# POWER_PCie.net
KiCad netlist of a schematic drawn in Altium Designer
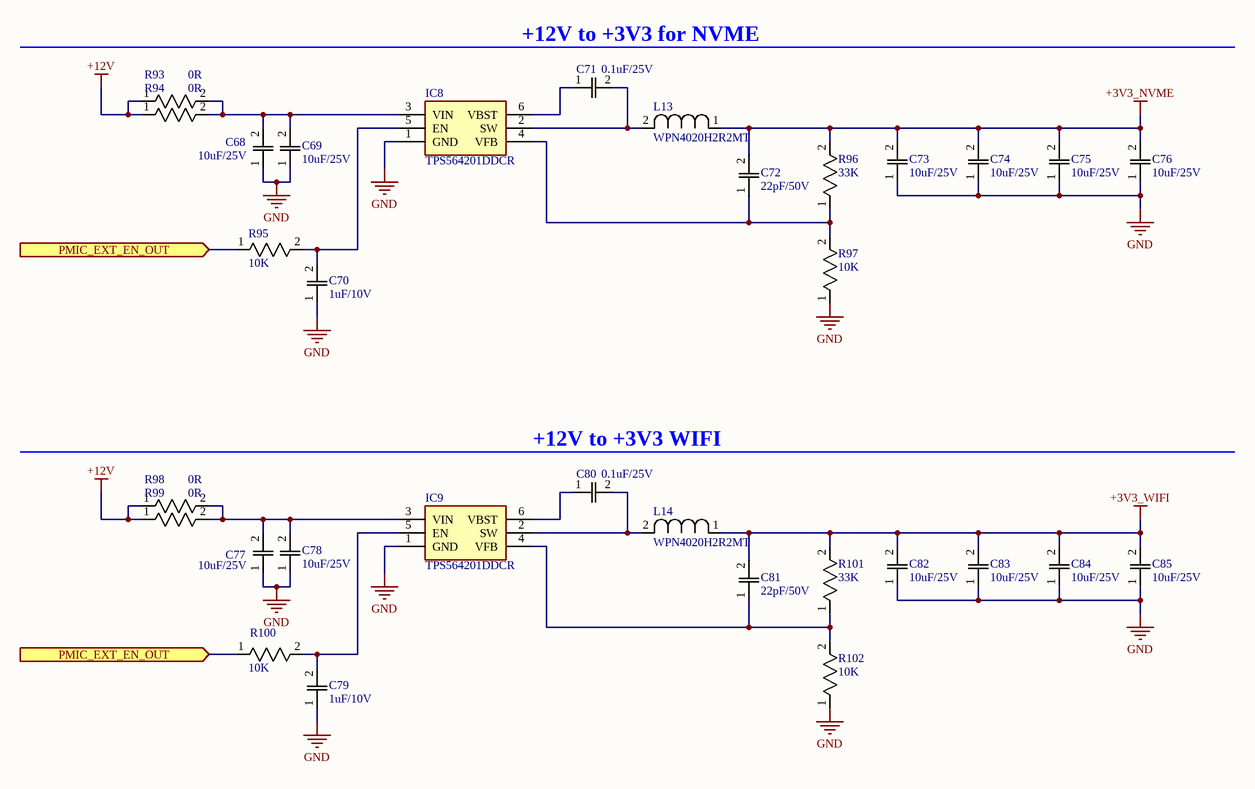
[diagram p0: POWER_PCie.SchDoc]

(export (version "E")
  (design (tool "Eeschema 10.0.6"))
  (components
    (comp (ref "C68")
      (value "10uF/25V")
      (footprint "CAPC220145_88N_KEM")
      (description "10uF / 25 VDC, +85degC, X5R Dielec, +/-10% ¦ KEMET C0805C106K3PACTU 0805")
      (fields
        (field (name "MANUFACTURER") "KEMET")
        (field (name "MANUFACTURER PART NUMBER") "C0805C106K3PACTU")
      )
      (libsource (lib "C0805C106K3PACTU") (part "C0805C106K3PACTU"))
    )
    (comp (ref "C69")
      (value "10uF/25V")
      (footprint "CAPC220145_88N_KEM")
      (description "10uF / 25 VDC, +85degC, X5R Dielec, +/-10% ¦ KEMET C0805C106K3PACTU 0805")
      (fields
        (field (name "MANUFACTURER") "KEMET")
        (field (name "MANUFACTURER PART NUMBER") "C0805C106K3PACTU")
      )
      (libsource (lib "C0805C106K3PACTU") (part "C0805C106K3PACTU"))
    )
    (comp (ref "C70")
      (value "1uF/10V")
      (footprint "CAPC220145_100N_KEM")
      (description "Multilayer Ceramic Capacitors MLCC - SMD/SMT 10V 1uF X7R 0805 10%")
      (fields
        (field (name "MANUFACTURER") "KEMET")
        (field (name "MANUFACTURER PART NUMBER") "C0805C105K8RACTU")
      )
      (libsource (lib "C0805C105K8RACTU") (part "C0805C105K8RACTU"))
    )
    (comp (ref "C71")
      (value "0.1uF/25V")
      (footprint "CAPC220145_88N_KEM")
      (description "0.1uF 25V X7R 10% SMD 0805 125C Plastic T/R")
      (fields
        (field (name "MANUFACTURER") "KEMET")
        (field (name "MANUFACTURER PART NUMBER") "C0805C104K3RACTU")
      )
      (libsource (lib "C0805C104K3RACTU") (part "C0805C104K3RACTU"))
    )
    (comp (ref "C72")
      (value "22pF/50V")
      (footprint "CAPC220145_145N_KEM")
      (description "Cap Ceramic 22pF 50V X7R 5% Pad SMD 0805 125°C T/R")
      (fields
        (field (name "MANUFACTURER") "KEMET")
        (field (name "MANUFACTURER PART NUMBER") "C0805C220J5RACTU")
      )
      (libsource (lib "C0805C220J5RACTU") (part "C0805C220J5RACTU"))
    )
    (comp (ref "C73")
      (value "10uF/25V")
      (footprint "CAPC220145_88N_KEM")
      (description "10uF / 25 VDC, +85degC, X5R Dielec, +/-10% ¦ KEMET C0805C106K3PACTU 0805")
      (fields
        (field (name "MANUFACTURER") "KEMET")
        (field (name "MANUFACTURER PART NUMBER") "C0805C106K3PACTU")
      )
      (libsource (lib "C0805C106K3PACTU") (part "C0805C106K3PACTU"))
    )
    (comp (ref "C74")
      (value "10uF/25V")
      (footprint "CAPC220145_88N_KEM")
      (description "10uF / 25 VDC, +85degC, X5R Dielec, +/-10% ¦ KEMET C0805C106K3PACTU 0805")
      (fields
        (field (name "MANUFACTURER") "KEMET")
        (field (name "MANUFACTURER PART NUMBER") "C0805C106K3PACTU")
      )
      (libsource (lib "C0805C106K3PACTU") (part "C0805C106K3PACTU"))
    )
    (comp (ref "C75")
      (value "10uF/25V")
      (footprint "CAPC220145_88N_KEM")
      (description "10uF / 25 VDC, +85degC, X5R Dielec, +/-10% ¦ KEMET C0805C106K3PACTU 0805")
      (fields
        (field (name "MANUFACTURER") "KEMET")
        (field (name "MANUFACTURER PART NUMBER") "C0805C106K3PACTU")
      )
      (libsource (lib "C0805C106K3PACTU") (part "C0805C106K3PACTU"))
    )
    (comp (ref "C76")
      (value "10uF/25V")
      (footprint "CAPC220145_88N_KEM")
      (description "10uF / 25 VDC, +85degC, X5R Dielec, +/-10% ¦ KEMET C0805C106K3PACTU 0805")
      (fields
        (field (name "MANUFACTURER") "KEMET")
        (field (name "MANUFACTURER PART NUMBER") "C0805C106K3PACTU")
      )
      (libsource (lib "C0805C106K3PACTU") (part "C0805C106K3PACTU"))
    )
    (comp (ref "C77")
      (value "10uF/25V")
      (footprint "CAPC220145_88N_KEM")
      (description "10uF / 25 VDC, +85degC, X5R Dielec, +/-10% ¦ KEMET C0805C106K3PACTU 0805")
      (fields
        (field (name "MANUFACTURER") "KEMET")
        (field (name "MANUFACTURER PART NUMBER") "C0805C106K3PACTU")
      )
      (libsource (lib "C0805C106K3PACTU") (part "C0805C106K3PACTU"))
    )
    (comp (ref "C78")
      (value "10uF/25V")
      (footprint "CAPC220145_88N_KEM")
      (description "10uF / 25 VDC, +85degC, X5R Dielec, +/-10% ¦ KEMET C0805C106K3PACTU 0805")
      (fields
        (field (name "MANUFACTURER") "KEMET")
        (field (name "MANUFACTURER PART NUMBER") "C0805C106K3PACTU")
      )
      (libsource (lib "C0805C106K3PACTU") (part "C0805C106K3PACTU"))
    )
    (comp (ref "C79")
      (value "1uF/10V")
      (footprint "CAPC220145_100N_KEM")
      (description "Multilayer Ceramic Capacitors MLCC - SMD/SMT 10V 1uF X7R 0805 10%")
      (fields
        (field (name "MANUFACTURER") "KEMET")
        (field (name "MANUFACTURER PART NUMBER") "C0805C105K8RACTU")
      )
      (libsource (lib "C0805C105K8RACTU") (part "C0805C105K8RACTU"))
    )
    (comp (ref "C80")
      (value "0.1uF/25V")
      (footprint "CAPC220145_88N_KEM")
      (description "0.1uF 25V X7R 10% SMD 0805 125C Plastic T/R")
      (fields
        (field (name "MANUFACTURER") "KEMET")
        (field (name "MANUFACTURER PART NUMBER") "C0805C104K3RACTU")
      )
      (libsource (lib "C0805C104K3RACTU") (part "C0805C104K3RACTU"))
    )
    (comp (ref "C81")
      (value "22pF/50V")
      (footprint "CAPC220145_145N_KEM")
      (description "Cap Ceramic 22pF 50V X7R 5% Pad SMD 0805 125°C T/R")
      (fields
        (field (name "MANUFACTURER") "KEMET")
        (field (name "MANUFACTURER PART NUMBER") "C0805C220J5RACTU")
      )
      (libsource (lib "C0805C220J5RACTU") (part "C0805C220J5RACTU"))
    )
    (comp (ref "C82")
      (value "10uF/25V")
      (footprint "CAPC220145_88N_KEM")
      (description "10uF / 25 VDC, +85degC, X5R Dielec, +/-10% ¦ KEMET C0805C106K3PACTU 0805")
      (fields
        (field (name "MANUFACTURER") "KEMET")
        (field (name "MANUFACTURER PART NUMBER") "C0805C106K3PACTU")
      )
      (libsource (lib "C0805C106K3PACTU") (part "C0805C106K3PACTU"))
    )
    (comp (ref "C83")
      (value "10uF/25V")
      (footprint "CAPC220145_88N_KEM")
      (description "10uF / 25 VDC, +85degC, X5R Dielec, +/-10% ¦ KEMET C0805C106K3PACTU 0805")
      (fields
        (field (name "MANUFACTURER") "KEMET")
        (field (name "MANUFACTURER PART NUMBER") "C0805C106K3PACTU")
      )
      (libsource (lib "C0805C106K3PACTU") (part "C0805C106K3PACTU"))
    )
    (comp (ref "C84")
      (value "10uF/25V")
      (footprint "CAPC220145_88N_KEM")
      (description "10uF / 25 VDC, +85degC, X5R Dielec, +/-10% ¦ KEMET C0805C106K3PACTU 0805")
      (fields
        (field (name "MANUFACTURER") "KEMET")
        (field (name "MANUFACTURER PART NUMBER") "C0805C106K3PACTU")
      )
      (libsource (lib "C0805C106K3PACTU") (part "C0805C106K3PACTU"))
    )
    (comp (ref "C85")
      (value "10uF/25V")
      (footprint "CAPC220145_88N_KEM")
      (description "10uF / 25 VDC, +85degC, X5R Dielec, +/-10% ¦ KEMET C0805C106K3PACTU 0805")
      (fields
        (field (name "MANUFACTURER") "KEMET")
        (field (name "MANUFACTURER PART NUMBER") "C0805C106K3PACTU")
      )
      (libsource (lib "C0805C106K3PACTU") (part "C0805C106K3PACTU"))
    )
    (comp (ref "IC8")
      (value "TPS564201DDCR")
      (footprint "SamacSys:SOT95P280X110-6N")
      (fields
        (field (name "MOUSER PART NUMBER") "595-TPS564201DDCR")
        (field (name "MANUFACTURER") "Texas Instruments")
      )
      (libsource (lib "SamacSys") (part "TPS564201DDCR"))
    )
    (comp (ref "IC9")
      (value "TPS564201DDCR")
      (footprint "SamacSys:SOT95P280X110-6N")
      (fields
        (field (name "MOUSER PART NUMBER") "595-TPS564201DDCR")
        (field (name "MANUFACTURER") "Texas Instruments")
      )
      (libsource (lib "SamacSys") (part "TPS564201DDCR"))
    )
    (comp (ref "L13")
      (value "WPN4020H2R2MT")
      (footprint "IND_WPN4020H_SNL")
      (description "2.2 µH Shielded Drum Core, Wirewound Inductor 4.3 A 48mOhm Max Nonstandard")
      (fields (field (name "MANUFACTURER") "Sunlord"))
      (libsource (lib "WPN4020H2R2MT") (part "WPN4020H2R2MT"))
    )
    (comp (ref "L14")
      (value "WPN4020H2R2MT")
      (footprint "IND_WPN4020H_SNL")
      (description "2.2 µH Shielded Drum Core, Wirewound Inductor 4.3 A 48mOhm Max Nonstandard")
      (fields (field (name "MANUFACTURER") "Sunlord"))
      (libsource (lib "WPN4020H2R2MT") (part "WPN4020H2R2MT"))
    )
    (comp (ref "R93")
      (value "0R")
      (footprint "SamacSys:ERJ3EKF1000V")
      (description "Zero Ohm Resistor, Jumper, 0603 [1608 Metric], Thick Film, 100 mW, 1 A, Surface Mount")
      (fields
        (field (name "MANUFACTURER_PART_NUMBER") "ERJ-3GEY0R00V")
        (field (name "MOUSER PART NUMBER") "667-ERJ-3GEY0R00V")
      )
      (libsource (lib "SamacSys") (part "ERJ-3GEY0R00V"))
    )
    (comp (ref "R94")
      (value "0R")
      (footprint "SamacSys:ERJ3EKF1000V")
      (description "Zero Ohm Resistor, Jumper, 0603 [1608 Metric], Thick Film, 100 mW, 1 A, Surface Mount")
      (fields
        (field (name "MANUFACTURER_PART_NUMBER") "ERJ-3GEY0R00V")
        (field (name "MOUSER PART NUMBER") "667-ERJ-3GEY0R00V")
      )
      (libsource (lib "SamacSys") (part "ERJ-3GEY0R00V"))
    )
    (comp (ref "R95")
      (value "10K")
      (footprint "SamacSys:ERJ3EKF1000V")
      (description "10K Ohm 5% Res Thick Film 0603  0.1W(1/10W) ±200ppm/C Pad SMD Automotive T/R")
      (fields
        (field (name "MANUFACTURER_PART_NUMBER") "ERJ-3GEYJ103V")
        (field (name "MOUSER PART NUMBER") "667-ERJ-3GEYJ103V")
      )
      (libsource (lib "SamacSys") (part "ERJ-3GEYJ103V"))
    )
    (comp (ref "R96")
      (value "33K")
      (footprint "SamacSys:ERJ3EKF1000V")
      (description "Thick Film Resistors - SMD 0603 33Kohms 5% AEC-Q200")
      (fields (field (name "MANUFACTURER_PART_NUMBER") "ERJ-3GEYJ333V"))
      (libsource (lib "SamacSys") (part "ERJ-3GEYJ333V"))
    )
    (comp (ref "R97")
      (value "10K")
      (footprint "SamacSys:ERJ3EKF1000V")
      (description "10K Ohm 5% Res Thick Film 0603  0.1W(1/10W) ±200ppm/C Pad SMD Automotive T/R")
      (fields
        (field (name "MANUFACTURER_PART_NUMBER") "ERJ-3GEYJ103V")
        (field (name "MOUSER PART NUMBER") "667-ERJ-3GEYJ103V")
      )
      (libsource (lib "SamacSys") (part "ERJ-3GEYJ103V"))
    )
    (comp (ref "R98")
      (value "0R")
      (footprint "SamacSys:ERJ3EKF1000V")
      (description "Zero Ohm Resistor, Jumper, 0603 [1608 Metric], Thick Film, 100 mW, 1 A, Surface Mount")
      (fields
        (field (name "MANUFACTURER_PART_NUMBER") "ERJ-3GEY0R00V")
        (field (name "MOUSER PART NUMBER") "667-ERJ-3GEY0R00V")
      )
      (libsource (lib "SamacSys") (part "ERJ-3GEY0R00V"))
    )
    (comp (ref "R99")
      (value "0R")
      (footprint "SamacSys:ERJ3EKF1000V")
      (description "Zero Ohm Resistor, Jumper, 0603 [1608 Metric], Thick Film, 100 mW, 1 A, Surface Mount")
      (fields
        (field (name "MANUFACTURER_PART_NUMBER") "ERJ-3GEY0R00V")
        (field (name "MOUSER PART NUMBER") "667-ERJ-3GEY0R00V")
      )
      (libsource (lib "SamacSys") (part "ERJ-3GEY0R00V"))
    )
    (comp (ref "R100")
      (value "10K")
      (footprint "SamacSys:ERJ3EKF1000V")
      (description "10K Ohm 5% Res Thick Film 0603  0.1W(1/10W) ±200ppm/C Pad SMD Automotive T/R")
      (fields
        (field (name "MANUFACTURER_PART_NUMBER") "ERJ-3GEYJ103V")
        (field (name "MOUSER PART NUMBER") "667-ERJ-3GEYJ103V")
      )
      (libsource (lib "SamacSys") (part "ERJ-3GEYJ103V"))
    )
    (comp (ref "R101")
      (value "33K")
      (footprint "SamacSys:ERJ3EKF1000V")
      (description "Thick Film Resistors - SMD 0603 33Kohms 5% AEC-Q200")
      (fields (field (name "MANUFACTURER_PART_NUMBER") "ERJ-3GEYJ333V"))
      (libsource (lib "SamacSys") (part "ERJ-3GEYJ333V"))
    )
    (comp (ref "R102")
      (value "10K")
      (footprint "SamacSys:ERJ3EKF1000V")
      (description "10K Ohm 5% Res Thick Film 0603  0.1W(1/10W) ±200ppm/C Pad SMD Automotive T/R")
      (fields
        (field (name "MANUFACTURER_PART_NUMBER") "ERJ-3GEYJ103V")
        (field (name "MOUSER PART NUMBER") "667-ERJ-3GEYJ103V")
      )
      (libsource (lib "SamacSys") (part "ERJ-3GEYJ103V"))
    )
  )
  (nets
    (net (code "1") (name "+3V3_NVME") (class "Default")
      (node (ref "C72") (pin "2") (pinfunction "2_2") (pintype "passive"))
      (node (ref "C73") (pin "2") (pinfunction "2_2") (pintype "passive"))
      (node (ref "C74") (pin "2") (pinfunction "2_2") (pintype "passive"))
      (node (ref "C75") (pin "2") (pinfunction "2_2") (pintype "passive"))
      (node (ref "C76") (pin "2") (pinfunction "2_2") (pintype "passive"))
      (node (ref "L13") (pin "1") (pinfunction "1_1") (pintype "passive"))
      (node (ref "R96") (pin "2") (pinfunction "2_2") (pintype "passive"))
    )
    (net (code "2") (name "+3V3_WIFI") (class "Default")
      (node (ref "C81") (pin "2") (pinfunction "2_2") (pintype "passive"))
      (node (ref "C82") (pin "2") (pinfunction "2_2") (pintype "passive"))
      (node (ref "C83") (pin "2") (pinfunction "2_2") (pintype "passive"))
      (node (ref "C84") (pin "2") (pinfunction "2_2") (pintype "passive"))
      (node (ref "C85") (pin "2") (pinfunction "2_2") (pintype "passive"))
      (node (ref "L14") (pin "1") (pinfunction "1_1") (pintype "passive"))
      (node (ref "R101") (pin "2") (pinfunction "2_2") (pintype "passive"))
    )
    (net (code "3") (name "+12V") (class "Default")
      (node (ref "R93") (pin "1") (pinfunction "1_1") (pintype "passive"))
      (node (ref "R94") (pin "1") (pinfunction "1_1") (pintype "passive"))
      (node (ref "R98") (pin "1") (pinfunction "1_1") (pintype "passive"))
      (node (ref "R99") (pin "1") (pinfunction "1_1") (pintype "passive"))
    )
    (net (code "4") (name "/PMIC_EXT_EN_OUT") (class "Default")
      (node (ref "R100") (pin "1") (pinfunction "1_1") (pintype "passive"))
      (node (ref "R95") (pin "1") (pinfunction "1_1") (pintype "passive"))
    )
    (net (code "5") (name "GND") (class "Default")
      (node (ref "C68") (pin "1") (pinfunction "1_1") (pintype "passive"))
      (node (ref "C69") (pin "1") (pinfunction "1_1") (pintype "passive"))
      (node (ref "C70") (pin "1") (pinfunction "1_1") (pintype "passive"))
      (node (ref "C73") (pin "1") (pinfunction "1_1") (pintype "passive"))
      (node (ref "C74") (pin "1") (pinfunction "1_1") (pintype "passive"))
      (node (ref "C75") (pin "1") (pinfunction "1_1") (pintype "passive"))
      (node (ref "C76") (pin "1") (pinfunction "1_1") (pintype "passive"))
      (node (ref "C77") (pin "1") (pinfunction "1_1") (pintype "passive"))
      (node (ref "C78") (pin "1") (pinfunction "1_1") (pintype "passive"))
      (node (ref "C79") (pin "1") (pinfunction "1_1") (pintype "passive"))
      (node (ref "C82") (pin "1") (pinfunction "1_1") (pintype "passive"))
      (node (ref "C83") (pin "1") (pinfunction "1_1") (pintype "passive"))
      (node (ref "C84") (pin "1") (pinfunction "1_1") (pintype "passive"))
      (node (ref "C85") (pin "1") (pinfunction "1_1") (pintype "passive"))
      (node (ref "IC8") (pin "1") (pinfunction "GND_1") (pintype "passive"))
      (node (ref "IC9") (pin "1") (pinfunction "GND_1") (pintype "passive"))
      (node (ref "R102") (pin "1") (pinfunction "1_1") (pintype "passive"))
      (node (ref "R97") (pin "1") (pinfunction "1_1") (pintype "passive"))
    )
    (net (code "6") (name "Net-(IC8-EN)") (class "Default")
      (node (ref "C70") (pin "2") (pinfunction "2_2") (pintype "passive"))
      (node (ref "IC8") (pin "5") (pinfunction "EN_5") (pintype "passive"))
      (node (ref "R95") (pin "2") (pinfunction "2_2") (pintype "passive"))
    )
    (net (code "7") (name "Net-(IC8-SW)") (class "Default")
      (node (ref "C71") (pin "2") (pinfunction "2_2") (pintype "passive"))
      (node (ref "IC8") (pin "2") (pinfunction "SW_2") (pintype "passive"))
      (node (ref "L13") (pin "2") (pinfunction "2_2") (pintype "passive"))
    )
    (net (code "8") (name "Net-(IC8-VBST)") (class "Default")
      (node (ref "C71") (pin "1") (pinfunction "1_1") (pintype "passive"))
      (node (ref "IC8") (pin "6") (pinfunction "VBST_6") (pintype "passive"))
    )
    (net (code "9") (name "Net-(IC8-VFB)") (class "Default")
      (node (ref "C72") (pin "1") (pinfunction "1_1") (pintype "passive"))
      (node (ref "IC8") (pin "4") (pinfunction "VFB_4") (pintype "passive"))
      (node (ref "R96") (pin "1") (pinfunction "1_1") (pintype "passive"))
      (node (ref "R97") (pin "2") (pinfunction "2_2") (pintype "passive"))
    )
    (net (code "10") (name "Net-(IC8-VIN)") (class "Default")
      (node (ref "C68") (pin "2") (pinfunction "2_2") (pintype "passive"))
      (node (ref "C69") (pin "2") (pinfunction "2_2") (pintype "passive"))
      (node (ref "IC8") (pin "3") (pinfunction "VIN_3") (pintype "passive"))
      (node (ref "R93") (pin "2") (pinfunction "2_2") (pintype "passive"))
      (node (ref "R94") (pin "2") (pinfunction "2_2") (pintype "passive"))
    )
    (net (code "11") (name "Net-(IC9-EN)") (class "Default")
      (node (ref "C79") (pin "2") (pinfunction "2_2") (pintype "passive"))
      (node (ref "IC9") (pin "5") (pinfunction "EN_5") (pintype "passive"))
      (node (ref "R100") (pin "2") (pinfunction "2_2") (pintype "passive"))
    )
    (net (code "12") (name "Net-(IC9-SW)") (class "Default")
      (node (ref "C80") (pin "2") (pinfunction "2_2") (pintype "passive"))
      (node (ref "IC9") (pin "2") (pinfunction "SW_2") (pintype "passive"))
      (node (ref "L14") (pin "2") (pinfunction "2_2") (pintype "passive"))
    )
    (net (code "13") (name "Net-(IC9-VBST)") (class "Default")
      (node (ref "C80") (pin "1") (pinfunction "1_1") (pintype "passive"))
      (node (ref "IC9") (pin "6") (pinfunction "VBST_6") (pintype "passive"))
    )
    (net (code "14") (name "Net-(IC9-VFB)") (class "Default")
      (node (ref "C81") (pin "1") (pinfunction "1_1") (pintype "passive"))
      (node (ref "IC9") (pin "4") (pinfunction "VFB_4") (pintype "passive"))
      (node (ref "R101") (pin "1") (pinfunction "1_1") (pintype "passive"))
      (node (ref "R102") (pin "2") (pinfunction "2_2") (pintype "passive"))
    )
    (net (code "15") (name "Net-(IC9-VIN)") (class "Default")
      (node (ref "C77") (pin "2") (pinfunction "2_2") (pintype "passive"))
      (node (ref "C78") (pin "2") (pinfunction "2_2") (pintype "passive"))
      (node (ref "IC9") (pin "3") (pinfunction "VIN_3") (pintype "passive"))
      (node (ref "R98") (pin "2") (pinfunction "2_2") (pintype "passive"))
      (node (ref "R99") (pin "2") (pinfunction "2_2") (pintype "passive"))
    )
  )
)
